# ACE.net
KiCad netlist of a schematic drawn in Altium Designer
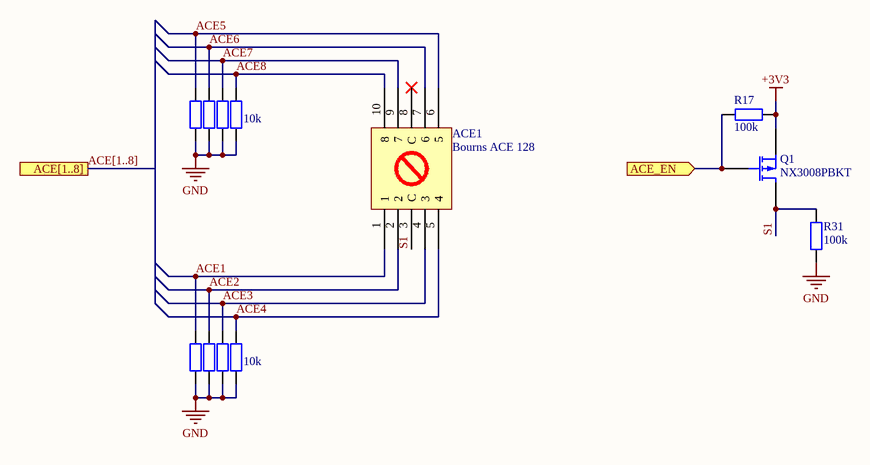
[diagram p0: ACE.SchDoc]

(export (version "E")
  (design (tool "Eeschema 10.0.6"))
  (components
    (comp (ref "ACE1")
      (value "Bourns ACE 128")
      (footprint "Bourns ACE 128")
      (libsource (lib "led_ring") (part "Bourns ACE 128"))
    )
    (comp (ref "Q1")
      (value "NX3008PBKT")
      (footprint "SOT95P230X110-3L")
      (description "P-Channel MOSFET")
      (fields (field (name "PUBLISHER") "Altium Limited"))
      (libsource (lib "Miscellaneous Devices") (part "MOSFET-P"))
    )
    (comp (ref "R17")
      (value "100k")
      (footprint "R1005_0402i_L")
      (description "R")
      (libsource (lib "General") (part "R"))
    )
    (comp (ref "R18")
      (value "10k")
      (footprint "R1005_0402i_L")
      (description "R")
      (libsource (lib "General") (part "R"))
    )
    (comp (ref "R19")
      (value "10k")
      (footprint "R1005_0402i_L")
      (description "R")
      (libsource (lib "General") (part "R"))
    )
    (comp (ref "R20")
      (value "10k")
      (footprint "R1005_0402i_L")
      (description "R")
      (libsource (lib "General") (part "R"))
    )
    (comp (ref "R21")
      (value "10k")
      (footprint "R1005_0402i_L")
      (description "R")
      (libsource (lib "General") (part "R"))
    )
    (comp (ref "R22")
      (value "10k")
      (footprint "R1005_0402i_L")
      (description "R")
      (libsource (lib "General") (part "R"))
    )
    (comp (ref "R23")
      (value "10k")
      (footprint "R1005_0402i_L")
      (description "R")
      (libsource (lib "General") (part "R"))
    )
    (comp (ref "R24")
      (value "10k")
      (footprint "R1005_0402i_L")
      (description "R")
      (libsource (lib "General") (part "R"))
    )
    (comp (ref "R25")
      (value "10k")
      (footprint "R1005_0402i_L")
      (description "R")
      (libsource (lib "General") (part "R"))
    )
    (comp (ref "R31")
      (value "100k")
      (footprint "R1005_0402i_L")
      (description "R")
      (libsource (lib "General") (part "R"))
    )
  )
  (nets
    (net (code "1") (name "+3V3") (class "Default")
      (node (ref "Q1") (pin "2") (pinfunction "S_2") (pintype "passive"))
      (node (ref "R17") (pin "2") (pintype "passive"))
    )
    (net (code "2") (name "/ACE1") (class "Default")
      (node (ref "ACE1") (pin "1") (pinfunction "1_1") (pintype "passive"))
      (node (ref "R22") (pin "2") (pintype "passive"))
    )
    (net (code "3") (name "/ACE2") (class "Default")
      (node (ref "ACE1") (pin "2") (pinfunction "2_2") (pintype "passive"))
      (node (ref "R23") (pin "2") (pintype "passive"))
    )
    (net (code "4") (name "/ACE3") (class "Default")
      (node (ref "ACE1") (pin "4") (pinfunction "3_4") (pintype "passive"))
      (node (ref "R24") (pin "2") (pintype "passive"))
    )
    (net (code "5") (name "/ACE4") (class "Default")
      (node (ref "ACE1") (pin "5") (pinfunction "4_5") (pintype "passive"))
      (node (ref "R25") (pin "2") (pintype "passive"))
    )
    (net (code "6") (name "/ACE5") (class "Default")
      (node (ref "ACE1") (pin "6") (pinfunction "5_6") (pintype "passive"))
      (node (ref "R18") (pin "2") (pintype "passive"))
    )
    (net (code "7") (name "/ACE6") (class "Default")
      (node (ref "ACE1") (pin "7") (pinfunction "6_7") (pintype "passive"))
      (node (ref "R19") (pin "2") (pintype "passive"))
    )
    (net (code "8") (name "/ACE7") (class "Default")
      (node (ref "ACE1") (pin "9") (pinfunction "7_9") (pintype "passive"))
      (node (ref "R20") (pin "2") (pintype "passive"))
    )
    (net (code "9") (name "/ACE8") (class "Default")
      (node (ref "ACE1") (pin "10") (pinfunction "8_10") (pintype "passive"))
      (node (ref "R21") (pin "2") (pintype "passive"))
    )
    (net (code "11") (name "/ACE_EN") (class "Default")
      (node (ref "Q1") (pin "1") (pinfunction "G_1") (pintype "passive"))
      (node (ref "R17") (pin "1") (pintype "passive"))
    )
    (net (code "12") (name "/S1") (class "Default")
      (node (ref "ACE1") (pin "3") (pinfunction "C_3") (pintype "passive"))
      (node (ref "Q1") (pin "3") (pinfunction "D_3") (pintype "passive"))
      (node (ref "R31") (pin "2") (pintype "passive"))
    )
    (net (code "13") (name "GND") (class "Default")
      (node (ref "R18") (pin "1") (pintype "passive"))
      (node (ref "R19") (pin "1") (pintype "passive"))
      (node (ref "R20") (pin "1") (pintype "passive"))
      (node (ref "R21") (pin "1") (pintype "passive"))
      (node (ref "R22") (pin "1") (pintype "passive"))
      (node (ref "R23") (pin "1") (pintype "passive"))
      (node (ref "R24") (pin "1") (pintype "passive"))
      (node (ref "R25") (pin "1") (pintype "passive"))
      (node (ref "R31") (pin "1") (pintype "passive"))
    )
    (net (code "14") (name "unconnected-(ACE1-C-Pad8)") (class "Default")
      (node (ref "ACE1") (pin "8") (pinfunction "C_8") (pintype "passive+no_connect"))
    )
  )
)
